# ZynqMIO.net
KiCad netlist of a schematic drawn in Altium Designer
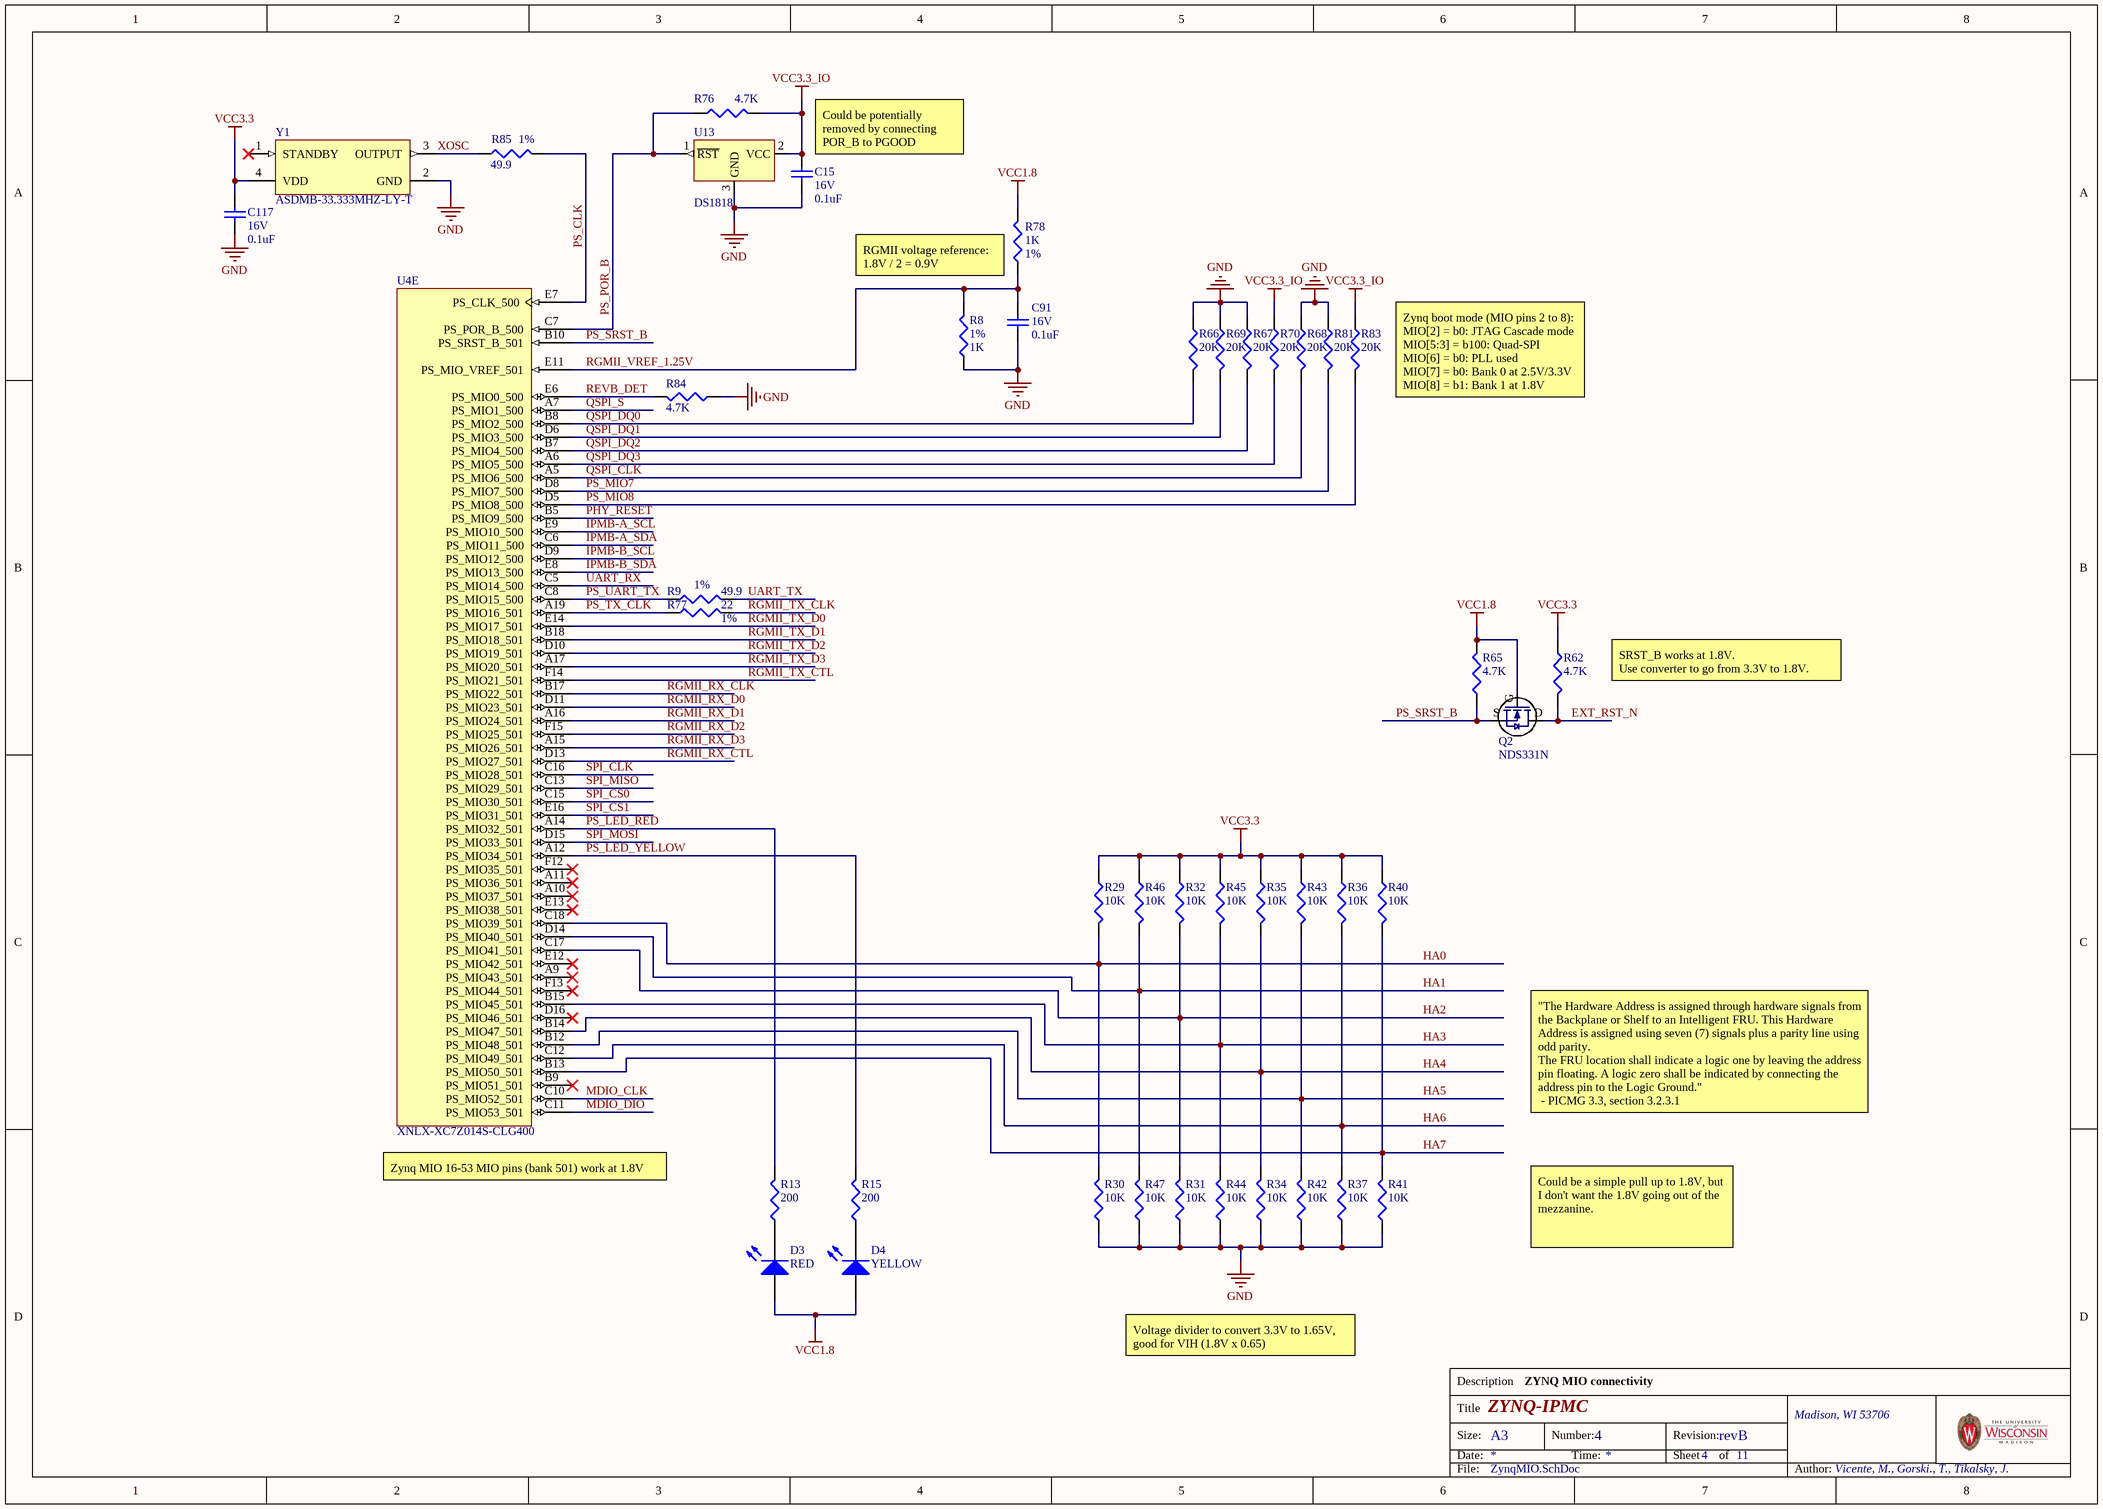
[diagram p0: ZynqMIO.SchDoc]

(export (version "E")
  (design (tool "Eeschema 10.0.6"))
  (components
    (comp (ref "C15")
      (value "0.1uF")
      (footprint "C0402_IPC_H")
      (description "Capacitor")
      (fields
        (field (name "RATING") "16V")
        (field (name "MANUFACTURER") "Murata")
        (field (name "PART") "GRM155R71C104KA88D")
      )
      (libsource (lib "CustomParts") (part "Cap"))
    )
    (comp (ref "C91")
      (value "0.1uF")
      (footprint "C0402_IPC_H")
      (description "Capacitor")
      (fields
        (field (name "RATING") "16V")
        (field (name "MANUFACTURER") "Murata")
        (field (name "PART") "GRM155R71C104KA88D")
      )
      (libsource (lib "CustomParts") (part "Cap"))
    )
    (comp (ref "C117")
      (value "0.1uF")
      (footprint "C0402_IPC_H")
      (description "Capacitor")
      (fields
        (field (name "RATING") "16V")
        (field (name "MANUFACTURER") "Murata")
        (field (name "PART") "GRM155R71C104KA88D")
      )
      (libsource (lib "CustomParts") (part "Cap"))
    )
    (comp (ref "D3")
      (value "RED")
      (footprint "LED0603_M")
      (description "Light Emitting Diode")
      (fields (field (name "MANUFACTURER") "Lite-On") (field (name "PART") "LTST-C190KRKT"))
      (libsource (lib "CustomParts") (part "LED"))
    )
    (comp (ref "D4")
      (value "YELLOW")
      (footprint "LED0603_M")
      (description "Light Emitting Diode")
      (fields (field (name "MANUFACTURER") "Lite-On") (field (name "PART") "LTST-C190KSKT"))
      (libsource (lib "CustomParts") (part "LED"))
    )
    (comp (ref "Q2")
      (value "NDS331N")
      (footprint "SOT23-H")
      (description "N-Channel   Logic Level Enhancement Mode Field Effect Transistor")
      (fields (field (name "MANUFACTURER") "Fairchild"))
      (libsource (lib "CustomParts") (part "NDS331N"))
    )
    (comp (ref "R8")
      (value "1K")
      (footprint "R0402_IPC_H")
      (description "Resistor")
      (fields
        (field (name "TOLERANCE") "1%")
        (field (name "MANUFACTURER") "Panasonic-ECG")
        (field (name "PART") "ERJ-2RKF1001X")
      )
      (libsource (lib "CustomParts") (part "Res"))
    )
    (comp (ref "R9")
      (value "49.9")
      (footprint "R0402_IPC_H")
      (description "Resistor")
      (fields
        (field (name "TOLERANCE") "1%")
        (field (name "MANUFACTURER") "Panasonic")
        (field (name "PART") "ERJ-2RKF49R9X")
      )
      (libsource (lib "CustomParts") (part "Res"))
    )
    (comp (ref "R13")
      (value "200")
      (footprint "R0402_IPC_H")
      (description "Resistor")
      (fields (field (name "TOLERANCE") "1%") (field (name "MANUFACTURER") "Panasonic-ECG"))
      (libsource (lib "CustomParts") (part "Res"))
    )
    (comp (ref "R15")
      (value "200")
      (footprint "R0402_IPC_H")
      (description "Resistor")
      (fields (field (name "TOLERANCE") "1%") (field (name "MANUFACTURER") "Panasonic-ECG"))
      (libsource (lib "CustomParts") (part "Res"))
    )
    (comp (ref "R29")
      (value "10K")
      (footprint "R0201_IPC_H")
      (description "Resistor")
      (fields (field (name "TOLERANCE") "1%") (field (name "MANUFACTURER") "Panasonic"))
      (libsource (lib "CustomParts") (part "Res"))
    )
    (comp (ref "R30")
      (value "10K")
      (footprint "R0201_IPC_H")
      (description "Resistor")
      (fields (field (name "TOLERANCE") "1%") (field (name "MANUFACTURER") "Panasonic"))
      (libsource (lib "CustomParts") (part "Res"))
    )
    (comp (ref "R31")
      (value "10K")
      (footprint "R0201_IPC_H")
      (description "Resistor")
      (fields (field (name "TOLERANCE") "1%") (field (name "MANUFACTURER") "Panasonic"))
      (libsource (lib "CustomParts") (part "Res"))
    )
    (comp (ref "R32")
      (value "10K")
      (footprint "R0201_IPC_H")
      (description "Resistor")
      (fields (field (name "TOLERANCE") "1%") (field (name "MANUFACTURER") "Panasonic"))
      (libsource (lib "CustomParts") (part "Res"))
    )
    (comp (ref "R34")
      (value "10K")
      (footprint "R0201_IPC_H")
      (description "Resistor")
      (fields (field (name "TOLERANCE") "1%") (field (name "MANUFACTURER") "Panasonic"))
      (libsource (lib "CustomParts") (part "Res"))
    )
    (comp (ref "R35")
      (value "10K")
      (footprint "R0201_IPC_H")
      (description "Resistor")
      (fields (field (name "TOLERANCE") "1%") (field (name "MANUFACTURER") "Panasonic"))
      (libsource (lib "CustomParts") (part "Res"))
    )
    (comp (ref "R36")
      (value "10K")
      (footprint "R0201_IPC_H")
      (description "Resistor")
      (fields (field (name "TOLERANCE") "1%") (field (name "MANUFACTURER") "Panasonic"))
      (libsource (lib "CustomParts") (part "Res"))
    )
    (comp (ref "R37")
      (value "10K")
      (footprint "R0201_IPC_H")
      (description "Resistor")
      (fields (field (name "TOLERANCE") "1%") (field (name "MANUFACTURER") "Panasonic"))
      (libsource (lib "CustomParts") (part "Res"))
    )
    (comp (ref "R40")
      (value "10K")
      (footprint "R0201_IPC_H")
      (description "Resistor")
      (fields (field (name "TOLERANCE") "1%") (field (name "MANUFACTURER") "Panasonic"))
      (libsource (lib "CustomParts") (part "Res"))
    )
    (comp (ref "R41")
      (value "10K")
      (footprint "R0201_IPC_H")
      (description "Resistor")
      (fields (field (name "TOLERANCE") "1%") (field (name "MANUFACTURER") "Panasonic"))
      (libsource (lib "CustomParts") (part "Res"))
    )
    (comp (ref "R42")
      (value "10K")
      (footprint "R0201_IPC_H")
      (description "Resistor")
      (fields (field (name "TOLERANCE") "1%") (field (name "MANUFACTURER") "Panasonic"))
      (libsource (lib "CustomParts") (part "Res"))
    )
    (comp (ref "R43")
      (value "10K")
      (footprint "R0201_IPC_H")
      (description "Resistor")
      (fields (field (name "TOLERANCE") "1%") (field (name "MANUFACTURER") "Panasonic"))
      (libsource (lib "CustomParts") (part "Res"))
    )
    (comp (ref "R44")
      (value "10K")
      (footprint "R0201_IPC_H")
      (description "Resistor")
      (fields (field (name "TOLERANCE") "1%") (field (name "MANUFACTURER") "Panasonic"))
      (libsource (lib "CustomParts") (part "Res"))
    )
    (comp (ref "R45")
      (value "10K")
      (footprint "R0201_IPC_H")
      (description "Resistor")
      (fields (field (name "TOLERANCE") "1%") (field (name "MANUFACTURER") "Panasonic"))
      (libsource (lib "CustomParts") (part "Res"))
    )
    (comp (ref "R46")
      (value "10K")
      (footprint "R0201_IPC_H")
      (description "Resistor")
      (fields (field (name "TOLERANCE") "1%") (field (name "MANUFACTURER") "Panasonic"))
      (libsource (lib "CustomParts") (part "Res"))
    )
    (comp (ref "R47")
      (value "10K")
      (footprint "R0201_IPC_H")
      (description "Resistor")
      (fields (field (name "TOLERANCE") "1%") (field (name "MANUFACTURER") "Panasonic"))
      (libsource (lib "CustomParts") (part "Res"))
    )
    (comp (ref "R62")
      (value "4.7K")
      (footprint "R0402_IPC_H")
      (description "Resistor")
      (fields (field (name "TOLERANCE") "1%") (field (name "MANUFACTURER") "Panasonic"))
      (libsource (lib "CustomParts") (part "Res"))
    )
    (comp (ref "R65")
      (value "4.7K")
      (footprint "R0402_IPC_H")
      (description "Resistor")
      (fields (field (name "TOLERANCE") "1%") (field (name "MANUFACTURER") "Panasonic"))
      (libsource (lib "CustomParts") (part "Res"))
    )
    (comp (ref "R66")
      (value "20K")
      (footprint "R0402_IPC_H")
      (description "Resistor")
      (fields (field (name "TOLERANCE") "1%") (field (name "MANUFACTURER") "Panasonic-ECG"))
      (libsource (lib "CustomParts") (part "Res"))
    )
    (comp (ref "R67")
      (value "20K")
      (footprint "R0402_IPC_H")
      (description "Resistor")
      (fields (field (name "TOLERANCE") "1%") (field (name "MANUFACTURER") "Panasonic-ECG"))
      (libsource (lib "CustomParts") (part "Res"))
    )
    (comp (ref "R68")
      (value "20K")
      (footprint "R0402_IPC_H")
      (description "Resistor")
      (fields (field (name "TOLERANCE") "1%") (field (name "MANUFACTURER") "Panasonic-ECG"))
      (libsource (lib "CustomParts") (part "Res"))
    )
    (comp (ref "R69")
      (value "20K")
      (footprint "R0402_IPC_H")
      (description "Resistor")
      (fields (field (name "TOLERANCE") "1%") (field (name "MANUFACTURER") "Panasonic-ECG"))
      (libsource (lib "CustomParts") (part "Res"))
    )
    (comp (ref "R70")
      (value "20K")
      (footprint "R0402_IPC_H")
      (description "Resistor")
      (fields (field (name "TOLERANCE") "1%") (field (name "MANUFACTURER") "Panasonic-ECG"))
      (libsource (lib "CustomParts") (part "Res"))
    )
    (comp (ref "R76")
      (value "4.7K")
      (footprint "R0402_IPC_H")
      (description "Resistor")
      (fields (field (name "TOLERANCE") "1%") (field (name "MANUFACTURER") "Panasonic"))
      (libsource (lib "CustomParts") (part "Res"))
    )
    (comp (ref "R77")
      (value "22")
      (footprint "R0201_IPC_H")
      (description "Resistor")
      (fields
        (field (name "TOLERANCE") "1%")
        (field (name "MANUFACTURER") "Panasonic")
        (field (name "PART") "ERJ-1GNF22R0C")
      )
      (libsource (lib "CustomParts") (part "Res"))
    )
    (comp (ref "R78")
      (value "1K")
      (footprint "R0402_IPC_H")
      (description "Resistor")
      (fields
        (field (name "TOLERANCE") "1%")
        (field (name "MANUFACTURER") "Panasonic-ECG")
        (field (name "PART") "ERJ-2RKF1001X")
      )
      (libsource (lib "CustomParts") (part "Res"))
    )
    (comp (ref "R81")
      (value "20K")
      (footprint "R0402_IPC_H")
      (description "Resistor")
      (fields (field (name "TOLERANCE") "1%") (field (name "MANUFACTURER") "Panasonic-ECG"))
      (libsource (lib "CustomParts") (part "Res"))
    )
    (comp (ref "R83")
      (value "20K")
      (footprint "R0402_IPC_H")
      (description "Resistor")
      (fields (field (name "TOLERANCE") "1%") (field (name "MANUFACTURER") "Panasonic-ECG"))
      (libsource (lib "CustomParts") (part "Res"))
    )
    (comp (ref "R84")
      (value "4.7K")
      (footprint "R0402_IPC_H")
      (description "Resistor")
      (fields (field (name "TOLERANCE") "1%") (field (name "MANUFACTURER") "Panasonic"))
      (libsource (lib "CustomParts") (part "Res"))
    )
    (comp (ref "R85")
      (value "49.9")
      (footprint "R0402_IPC_H")
      (description "Resistor")
      (fields
        (field (name "TOLERANCE") "1%")
        (field (name "MANUFACTURER") "Panasonic")
        (field (name "PART") "ERJ-2RKF49R9X")
      )
      (libsource (lib "CustomParts") (part "Res"))
    )
    (comp (ref "U4")
      (value "XNLX-XC7Z014S-CLG400")
      (footprint "CLG400")
      (fields (field (name "MANUFACTURER") "Xilinx") (field (name "PART") "XC7Z014S-1CLG400C"))
      (libsource (lib "CustomParts") (part "XNLX-XC7Z020-CLG400"))
    )
    (comp (ref "U13")
      (value "DS1818")
      (footprint "SOT23-H")
      (description "3.3V EconoReset with Pushbutton")
      (fields (field (name "MANUFACTURER") "Maxim") (field (name "PART") "DS1818R-10"))
      (libsource (lib "CustomParts") (part "DS1818"))
    )
    (comp (ref "Y1")
      (value "ASDMB-33.333MHZ-LY-T")
      (footprint "ABRA-ASDMB-4_V")
      (fields
        (field (name "PARTNUMBER") "ASDMB-3.6864MHZ-LC-T")
        (field (name "MANUFACTURER") "Abracon")
        (field (name "PART") "ASDMB-33.333MHZ-LY")
      )
      (libsource (lib "altium-import") (part "root_0_CMP-0728-00001-1_"))
    )
  )
  (nets
    (net (code "1") (name "/EXT_RST_N") (class "Default")
      (node (ref "Q2") (pin "D") (pinfunction "D_D") (pintype "passive"))
      (node (ref "R62") (pin "2") (pinfunction "2_2") (pintype "passive"))
    )
    (net (code "2") (name "/HA0") (class "Default")
      (node (ref "R29") (pin "2") (pinfunction "2_2") (pintype "passive"))
      (node (ref "R30") (pin "2") (pinfunction "2_2") (pintype "passive"))
      (node (ref "U4") (pin "C18") (pinfunction "PS_MIO39_501_C18") (pintype "bidirectional"))
    )
    (net (code "3") (name "/HA1") (class "Default")
      (node (ref "R46") (pin "2") (pinfunction "2_2") (pintype "passive"))
      (node (ref "R47") (pin "2") (pinfunction "2_2") (pintype "passive"))
      (node (ref "U4") (pin "D14") (pinfunction "PS_MIO40_501_D14") (pintype "bidirectional"))
    )
    (net (code "4") (name "/HA2") (class "Default")
      (node (ref "R31") (pin "2") (pinfunction "2_2") (pintype "passive"))
      (node (ref "R32") (pin "2") (pinfunction "2_2") (pintype "passive"))
      (node (ref "U4") (pin "C17") (pinfunction "PS_MIO41_501_C17") (pintype "bidirectional"))
    )
    (net (code "5") (name "/HA3") (class "Default")
      (node (ref "R44") (pin "2") (pinfunction "2_2") (pintype "passive"))
      (node (ref "R45") (pin "2") (pinfunction "2_2") (pintype "passive"))
      (node (ref "U4") (pin "B15") (pinfunction "PS_MIO45_501_B15") (pintype "bidirectional"))
    )
    (net (code "6") (name "/HA4") (class "Default")
      (node (ref "R34") (pin "2") (pinfunction "2_2") (pintype "passive"))
      (node (ref "R35") (pin "2") (pinfunction "2_2") (pintype "passive"))
      (node (ref "U4") (pin "B14") (pinfunction "PS_MIO47_501_B14") (pintype "bidirectional"))
    )
    (net (code "7") (name "/HA5") (class "Default")
      (node (ref "R42") (pin "2") (pinfunction "2_2") (pintype "passive"))
      (node (ref "R43") (pin "2") (pinfunction "2_2") (pintype "passive"))
      (node (ref "U4") (pin "B12") (pinfunction "PS_MIO48_501_B12") (pintype "bidirectional"))
    )
    (net (code "8") (name "/HA6") (class "Default")
      (node (ref "R36") (pin "2") (pinfunction "2_2") (pintype "passive"))
      (node (ref "R37") (pin "2") (pinfunction "2_2") (pintype "passive"))
      (node (ref "U4") (pin "C12") (pinfunction "PS_MIO49_501_C12") (pintype "bidirectional"))
    )
    (net (code "9") (name "/HA7") (class "Default")
      (node (ref "R40") (pin "2") (pinfunction "2_2") (pintype "passive"))
      (node (ref "R41") (pin "2") (pinfunction "2_2") (pintype "passive"))
      (node (ref "U4") (pin "B13") (pinfunction "PS_MIO50_501_B13") (pintype "bidirectional"))
    )
    (net (code "10") (name "/IPMB-A_SCL") (class "Default")
      (node (ref "U4") (pin "E9") (pinfunction "PS_MIO10_500_E9") (pintype "bidirectional"))
    )
    (net (code "11") (name "/IPMB-A_SDA") (class "Default")
      (node (ref "U4") (pin "C6") (pinfunction "PS_MIO11_500_C6") (pintype "bidirectional"))
    )
    (net (code "12") (name "/IPMB-B_SCL") (class "Default")
      (node (ref "U4") (pin "D9") (pinfunction "PS_MIO12_500_D9") (pintype "bidirectional"))
    )
    (net (code "13") (name "/IPMB-B_SDA") (class "Default")
      (node (ref "U4") (pin "E8") (pinfunction "PS_MIO13_500_E8") (pintype "bidirectional"))
    )
    (net (code "14") (name "/MDIO_CLK") (class "Default")
      (node (ref "U4") (pin "C10") (pinfunction "PS_MIO52_501_C10") (pintype "bidirectional"))
    )
    (net (code "15") (name "/MDIO_DIO") (class "Default")
      (node (ref "U4") (pin "C11") (pinfunction "PS_MIO53_501_C11") (pintype "bidirectional"))
    )
    (net (code "16") (name "/PHY_RESET") (class "Default")
      (node (ref "U4") (pin "B5") (pinfunction "PS_MIO9_500_B5") (pintype "bidirectional"))
    )
    (net (code "17") (name "/PS_CLK") (class "Default")
      (node (ref "R85") (pin "1") (pinfunction "1_1") (pintype "passive"))
      (node (ref "U4") (pin "E7") (pinfunction "PS_CLK_500_E7") (pintype "input"))
    )
    (net (code "18") (name "/PS_LED_RED") (class "Default")
      (node (ref "R13") (pin "2") (pinfunction "2_2") (pintype "passive"))
      (node (ref "U4") (pin "A14") (pinfunction "PS_MIO32_501_A14") (pintype "bidirectional"))
    )
    (net (code "19") (name "/PS_LED_YELLOW") (class "Default")
      (node (ref "R15") (pin "2") (pinfunction "2_2") (pintype "passive"))
      (node (ref "U4") (pin "A12") (pinfunction "PS_MIO34_501_A12") (pintype "bidirectional"))
    )
    (net (code "20") (name "/PS_MIO7") (class "Default")
      (node (ref "R81") (pin "2") (pinfunction "2_2") (pintype "passive"))
      (node (ref "U4") (pin "D8") (pinfunction "PS_MIO7_500_D8") (pintype "bidirectional"))
    )
    (net (code "21") (name "/PS_MIO8") (class "Default")
      (node (ref "R83") (pin "2") (pinfunction "2_2") (pintype "passive"))
      (node (ref "U4") (pin "D5") (pinfunction "PS_MIO8_500_D5") (pintype "bidirectional"))
    )
    (net (code "22") (name "/PS_POR_B") (class "Default")
      (node (ref "R76") (pin "2") (pinfunction "2_2") (pintype "passive"))
      (node (ref "U13") (pin "1") (pinfunction "~{RST}_1") (pintype "output"))
      (node (ref "U4") (pin "C7") (pinfunction "PS_POR_B_500_C7") (pintype "input"))
    )
    (net (code "23") (name "/PS_SRST_B") (class "Default")
      (node (ref "Q2") (pin "S") (pinfunction "S_S") (pintype "passive"))
      (node (ref "R65") (pin "1") (pinfunction "1_1") (pintype "passive"))
      (node (ref "U4") (pin "B10") (pinfunction "PS_SRST_B_501_B10") (pintype "input"))
    )
    (net (code "24") (name "/PS_TX_CLK") (class "Default")
      (node (ref "R77") (pin "1") (pinfunction "1_1") (pintype "passive"))
      (node (ref "U4") (pin "A19") (pinfunction "PS_MIO16_501_A19") (pintype "bidirectional"))
    )
    (net (code "25") (name "/PS_UART_TX") (class "Default")
      (node (ref "R9") (pin "2") (pinfunction "2_2") (pintype "passive"))
      (node (ref "U4") (pin "C8") (pinfunction "PS_MIO15_500_C8") (pintype "bidirectional"))
    )
    (net (code "26") (name "/QSPI_CLK") (class "Default")
      (node (ref "R68") (pin "2") (pinfunction "2_2") (pintype "passive"))
      (node (ref "U4") (pin "A5") (pinfunction "PS_MIO6_500_A5") (pintype "bidirectional"))
    )
    (net (code "27") (name "/QSPI_DQ0") (class "Default")
      (node (ref "R66") (pin "2") (pinfunction "2_2") (pintype "passive"))
      (node (ref "U4") (pin "B8") (pinfunction "PS_MIO2_500_B8") (pintype "bidirectional"))
    )
    (net (code "28") (name "/QSPI_DQ1") (class "Default")
      (node (ref "R69") (pin "2") (pinfunction "2_2") (pintype "passive"))
      (node (ref "U4") (pin "D6") (pinfunction "PS_MIO3_500_D6") (pintype "bidirectional"))
    )
    (net (code "29") (name "/QSPI_DQ2") (class "Default")
      (node (ref "R67") (pin "2") (pinfunction "2_2") (pintype "passive"))
      (node (ref "U4") (pin "B7") (pinfunction "PS_MIO4_500_B7") (pintype "bidirectional"))
    )
    (net (code "30") (name "/QSPI_DQ3") (class "Default")
      (node (ref "R70") (pin "2") (pinfunction "2_2") (pintype "passive"))
      (node (ref "U4") (pin "A6") (pinfunction "PS_MIO5_500_A6") (pintype "bidirectional"))
    )
    (net (code "31") (name "/QSPI_S") (class "Default")
      (node (ref "U4") (pin "A7") (pinfunction "PS_MIO1_500_A7") (pintype "bidirectional"))
    )
    (net (code "32") (name "/REVB_DET") (class "Default")
      (node (ref "R84") (pin "2") (pinfunction "2_2") (pintype "passive"))
      (node (ref "U4") (pin "E6") (pinfunction "PS_MIO0_500_E6") (pintype "bidirectional"))
    )
    (net (code "33") (name "/RGMII_RX_CLK") (class "Default")
      (node (ref "U4") (pin "B17") (pinfunction "PS_MIO22_501_B17") (pintype "bidirectional"))
    )
    (net (code "34") (name "/RGMII_RX_CTL") (class "Default")
      (node (ref "U4") (pin "D13") (pinfunction "PS_MIO27_501_D13") (pintype "bidirectional"))
    )
    (net (code "35") (name "/RGMII_RX_D0") (class "Default")
      (node (ref "U4") (pin "D11") (pinfunction "PS_MIO23_501_D11") (pintype "bidirectional"))
    )
    (net (code "36") (name "/RGMII_RX_D1") (class "Default")
      (node (ref "U4") (pin "A16") (pinfunction "PS_MIO24_501_A16") (pintype "bidirectional"))
    )
    (net (code "37") (name "/RGMII_RX_D2") (class "Default")
      (node (ref "U4") (pin "F15") (pinfunction "PS_MIO25_501_F15") (pintype "bidirectional"))
    )
    (net (code "38") (name "/RGMII_RX_D3") (class "Default")
      (node (ref "U4") (pin "A15") (pinfunction "PS_MIO26_501_A15") (pintype "bidirectional"))
    )
    (net (code "39") (name "/RGMII_TX_CLK") (class "Default")
      (node (ref "R77") (pin "2") (pinfunction "2_2") (pintype "passive"))
    )
    (net (code "40") (name "/RGMII_TX_CTL") (class "Default")
      (node (ref "U4") (pin "F14") (pinfunction "PS_MIO21_501_F14") (pintype "bidirectional"))
    )
    (net (code "41") (name "/RGMII_TX_D0") (class "Default")
      (node (ref "U4") (pin "E14") (pinfunction "PS_MIO17_501_E14") (pintype "bidirectional"))
    )
    (net (code "42") (name "/RGMII_TX_D1") (class "Default")
      (node (ref "U4") (pin "B18") (pinfunction "PS_MIO18_501_B18") (pintype "bidirectional"))
    )
    (net (code "43") (name "/RGMII_TX_D2") (class "Default")
      (node (ref "U4") (pin "D10") (pinfunction "PS_MIO19_501_D10") (pintype "bidirectional"))
    )
    (net (code "44") (name "/RGMII_TX_D3") (class "Default")
      (node (ref "U4") (pin "A17") (pinfunction "PS_MIO20_501_A17") (pintype "bidirectional"))
    )
    (net (code "45") (name "/RGMII_VREF_1.25V") (class "Default")
      (node (ref "C91") (pin "2") (pinfunction "2_2") (pintype "passive"))
      (node (ref "R78") (pin "2") (pinfunction "2_2") (pintype "passive"))
      (node (ref "R8") (pin "1") (pinfunction "1_1") (pintype "passive"))
      (node (ref "U4") (pin "E11") (pinfunction "PS_MIO_VREF_501_E11") (pintype "input"))
    )
    (net (code "46") (name "/SPI_CLK") (class "Default")
      (node (ref "U4") (pin "C16") (pinfunction "PS_MIO28_501_C16") (pintype "bidirectional"))
    )
    (net (code "47") (name "/SPI_CS0") (class "Default")
      (node (ref "U4") (pin "C15") (pinfunction "PS_MIO30_501_C15") (pintype "bidirectional"))
    )
    (net (code "48") (name "/SPI_CS1") (class "Default")
      (node (ref "U4") (pin "E16") (pinfunction "PS_MIO31_501_E16") (pintype "bidirectional"))
    )
    (net (code "49") (name "/SPI_MISO") (class "Default")
      (node (ref "U4") (pin "C13") (pinfunction "PS_MIO29_501_C13") (pintype "bidirectional"))
    )
    (net (code "50") (name "/SPI_MOSI") (class "Default")
      (node (ref "U4") (pin "D15") (pinfunction "PS_MIO33_501_D15") (pintype "bidirectional"))
    )
    (net (code "51") (name "/UART_RX") (class "Default")
      (node (ref "U4") (pin "C5") (pinfunction "PS_MIO14_500_C5") (pintype "bidirectional"))
    )
    (net (code "52") (name "/UART_TX") (class "Default")
      (node (ref "R9") (pin "1") (pinfunction "1_1") (pintype "passive"))
    )
    (net (code "53") (name "/XOSC") (class "Default")
      (node (ref "R85") (pin "2") (pinfunction "2_2") (pintype "passive"))
      (node (ref "Y1") (pin "3") (pinfunction "OUTPUT_3") (pintype "output"))
    )
    (net (code "54") (name "GND") (class "Default")
      (node (ref "C117") (pin "1") (pinfunction "1_1") (pintype "passive"))
      (node (ref "C15") (pin "1") (pinfunction "1_1") (pintype "passive"))
      (node (ref "C91") (pin "1") (pinfunction "1_1") (pintype "passive"))
      (node (ref "R30") (pin "1") (pinfunction "1_1") (pintype "passive"))
      (node (ref "R31") (pin "1") (pinfunction "1_1") (pintype "passive"))
      (node (ref "R34") (pin "1") (pinfunction "1_1") (pintype "passive"))
      (node (ref "R37") (pin "1") (pinfunction "1_1") (pintype "passive"))
      (node (ref "R41") (pin "1") (pinfunction "1_1") (pintype "passive"))
      (node (ref "R42") (pin "1") (pinfunction "1_1") (pintype "passive"))
      (node (ref "R44") (pin "1") (pinfunction "1_1") (pintype "passive"))
      (node (ref "R47") (pin "1") (pinfunction "1_1") (pintype "passive"))
      (node (ref "R66") (pin "1") (pinfunction "1_1") (pintype "passive"))
      (node (ref "R67") (pin "1") (pinfunction "1_1") (pintype "passive"))
      (node (ref "R68") (pin "1") (pinfunction "1_1") (pintype "passive"))
      (node (ref "R69") (pin "1") (pinfunction "1_1") (pintype "passive"))
      (node (ref "R8") (pin "2") (pinfunction "2_2") (pintype "passive"))
      (node (ref "R81") (pin "1") (pinfunction "1_1") (pintype "passive"))
      (node (ref "R84") (pin "1") (pinfunction "1_1") (pintype "passive"))
      (node (ref "U13") (pin "3") (pinfunction "GND_3") (pintype "passive"))
      (node (ref "Y1") (pin "2") (pinfunction "GND_2") (pintype "power_in"))
    )
    (net (code "55") (name "Net-(D3-K)") (class "Default")
      (node (ref "D3") (pin "2") (pinfunction "K_2") (pintype "passive"))
      (node (ref "R13") (pin "1") (pinfunction "1_1") (pintype "passive"))
    )
    (net (code "56") (name "Net-(D4-K)") (class "Default")
      (node (ref "D4") (pin "2") (pinfunction "K_2") (pintype "passive"))
      (node (ref "R15") (pin "1") (pinfunction "1_1") (pintype "passive"))
    )
    (net (code "57") (name "VCC1.8") (class "Default")
      (node (ref "D3") (pin "1") (pinfunction "A_1") (pintype "passive"))
      (node (ref "D4") (pin "1") (pinfunction "A_1") (pintype "passive"))
      (node (ref "Q2") (pin "G") (pinfunction "G_G") (pintype "passive"))
      (node (ref "R65") (pin "2") (pinfunction "2_2") (pintype "passive"))
      (node (ref "R78") (pin "1") (pinfunction "1_1") (pintype "passive"))
    )
    (net (code "58") (name "VCC3.3") (class "Default")
      (node (ref "C117") (pin "2") (pinfunction "2_2") (pintype "passive"))
      (node (ref "R29") (pin "1") (pinfunction "1_1") (pintype "passive"))
      (node (ref "R32") (pin "1") (pinfunction "1_1") (pintype "passive"))
      (node (ref "R35") (pin "1") (pinfunction "1_1") (pintype "passive"))
      (node (ref "R36") (pin "1") (pinfunction "1_1") (pintype "passive"))
      (node (ref "R40") (pin "1") (pinfunction "1_1") (pintype "passive"))
      (node (ref "R43") (pin "1") (pinfunction "1_1") (pintype "passive"))
      (node (ref "R45") (pin "1") (pinfunction "1_1") (pintype "passive"))
      (node (ref "R46") (pin "1") (pinfunction "1_1") (pintype "passive"))
      (node (ref "R62") (pin "1") (pinfunction "1_1") (pintype "passive"))
      (node (ref "Y1") (pin "4") (pinfunction "VDD_4") (pintype "power_in"))
    )
    (net (code "59") (name "VCC3.3_IO") (class "Default")
      (node (ref "C15") (pin "2") (pinfunction "2_2") (pintype "passive"))
      (node (ref "R70") (pin "1") (pinfunction "1_1") (pintype "passive"))
      (node (ref "R76") (pin "1") (pinfunction "1_1") (pintype "passive"))
      (node (ref "R83") (pin "1") (pinfunction "1_1") (pintype "passive"))
      (node (ref "U13") (pin "2") (pinfunction "VCC_2") (pintype "passive"))
    )
    (net (code "60") (name "unconnected-(U4E-PS_MIO35_501-PadF12)") (class "Default")
      (node (ref "U4") (pin "F12") (pinfunction "PS_MIO35_501_F12") (pintype "bidirectional+no_connect"))
    )
    (net (code "61") (name "unconnected-(U4E-PS_MIO36_501-PadA11)") (class "Default")
      (node (ref "U4") (pin "A11") (pinfunction "PS_MIO36_501_A11") (pintype "bidirectional+no_connect"))
    )
    (net (code "62") (name "unconnected-(U4E-PS_MIO37_501-PadA10)") (class "Default")
      (node (ref "U4") (pin "A10") (pinfunction "PS_MIO37_501_A10") (pintype "bidirectional+no_connect"))
    )
    (net (code "63") (name "unconnected-(U4E-PS_MIO38_501-PadE13)") (class "Default")
      (node (ref "U4") (pin "E13") (pinfunction "PS_MIO38_501_E13") (pintype "bidirectional+no_connect"))
    )
    (net (code "64") (name "unconnected-(U4E-PS_MIO42_501-PadE12)") (class "Default")
      (node (ref "U4") (pin "E12") (pinfunction "PS_MIO42_501_E12") (pintype "bidirectional+no_connect"))
    )
    (net (code "65") (name "unconnected-(U4E-PS_MIO43_501-PadA9)") (class "Default")
      (node (ref "U4") (pin "A9") (pinfunction "PS_MIO43_501_A9") (pintype "bidirectional+no_connect"))
    )
    (net (code "66") (name "unconnected-(U4E-PS_MIO44_501-PadF13)") (class "Default")
      (node (ref "U4") (pin "F13") (pinfunction "PS_MIO44_501_F13") (pintype "bidirectional+no_connect"))
    )
    (net (code "67") (name "unconnected-(U4E-PS_MIO46_501-PadD16)") (class "Default")
      (node (ref "U4") (pin "D16") (pinfunction "PS_MIO46_501_D16") (pintype "bidirectional+no_connect"))
    )
    (net (code "68") (name "unconnected-(U4E-PS_MIO51_501-PadB9)") (class "Default")
      (node (ref "U4") (pin "B9") (pinfunction "PS_MIO51_501_B9") (pintype "bidirectional+no_connect"))
    )
    (net (code "69") (name "unconnected-(Y1-STANDBY-Pad1)") (class "Default")
      (node (ref "Y1") (pin "1") (pinfunction "STANDBY_1") (pintype "input+no_connect"))
    )
  )
)
